# Sheet1.net
KiCad netlist of a schematic drawn in Altium Designer
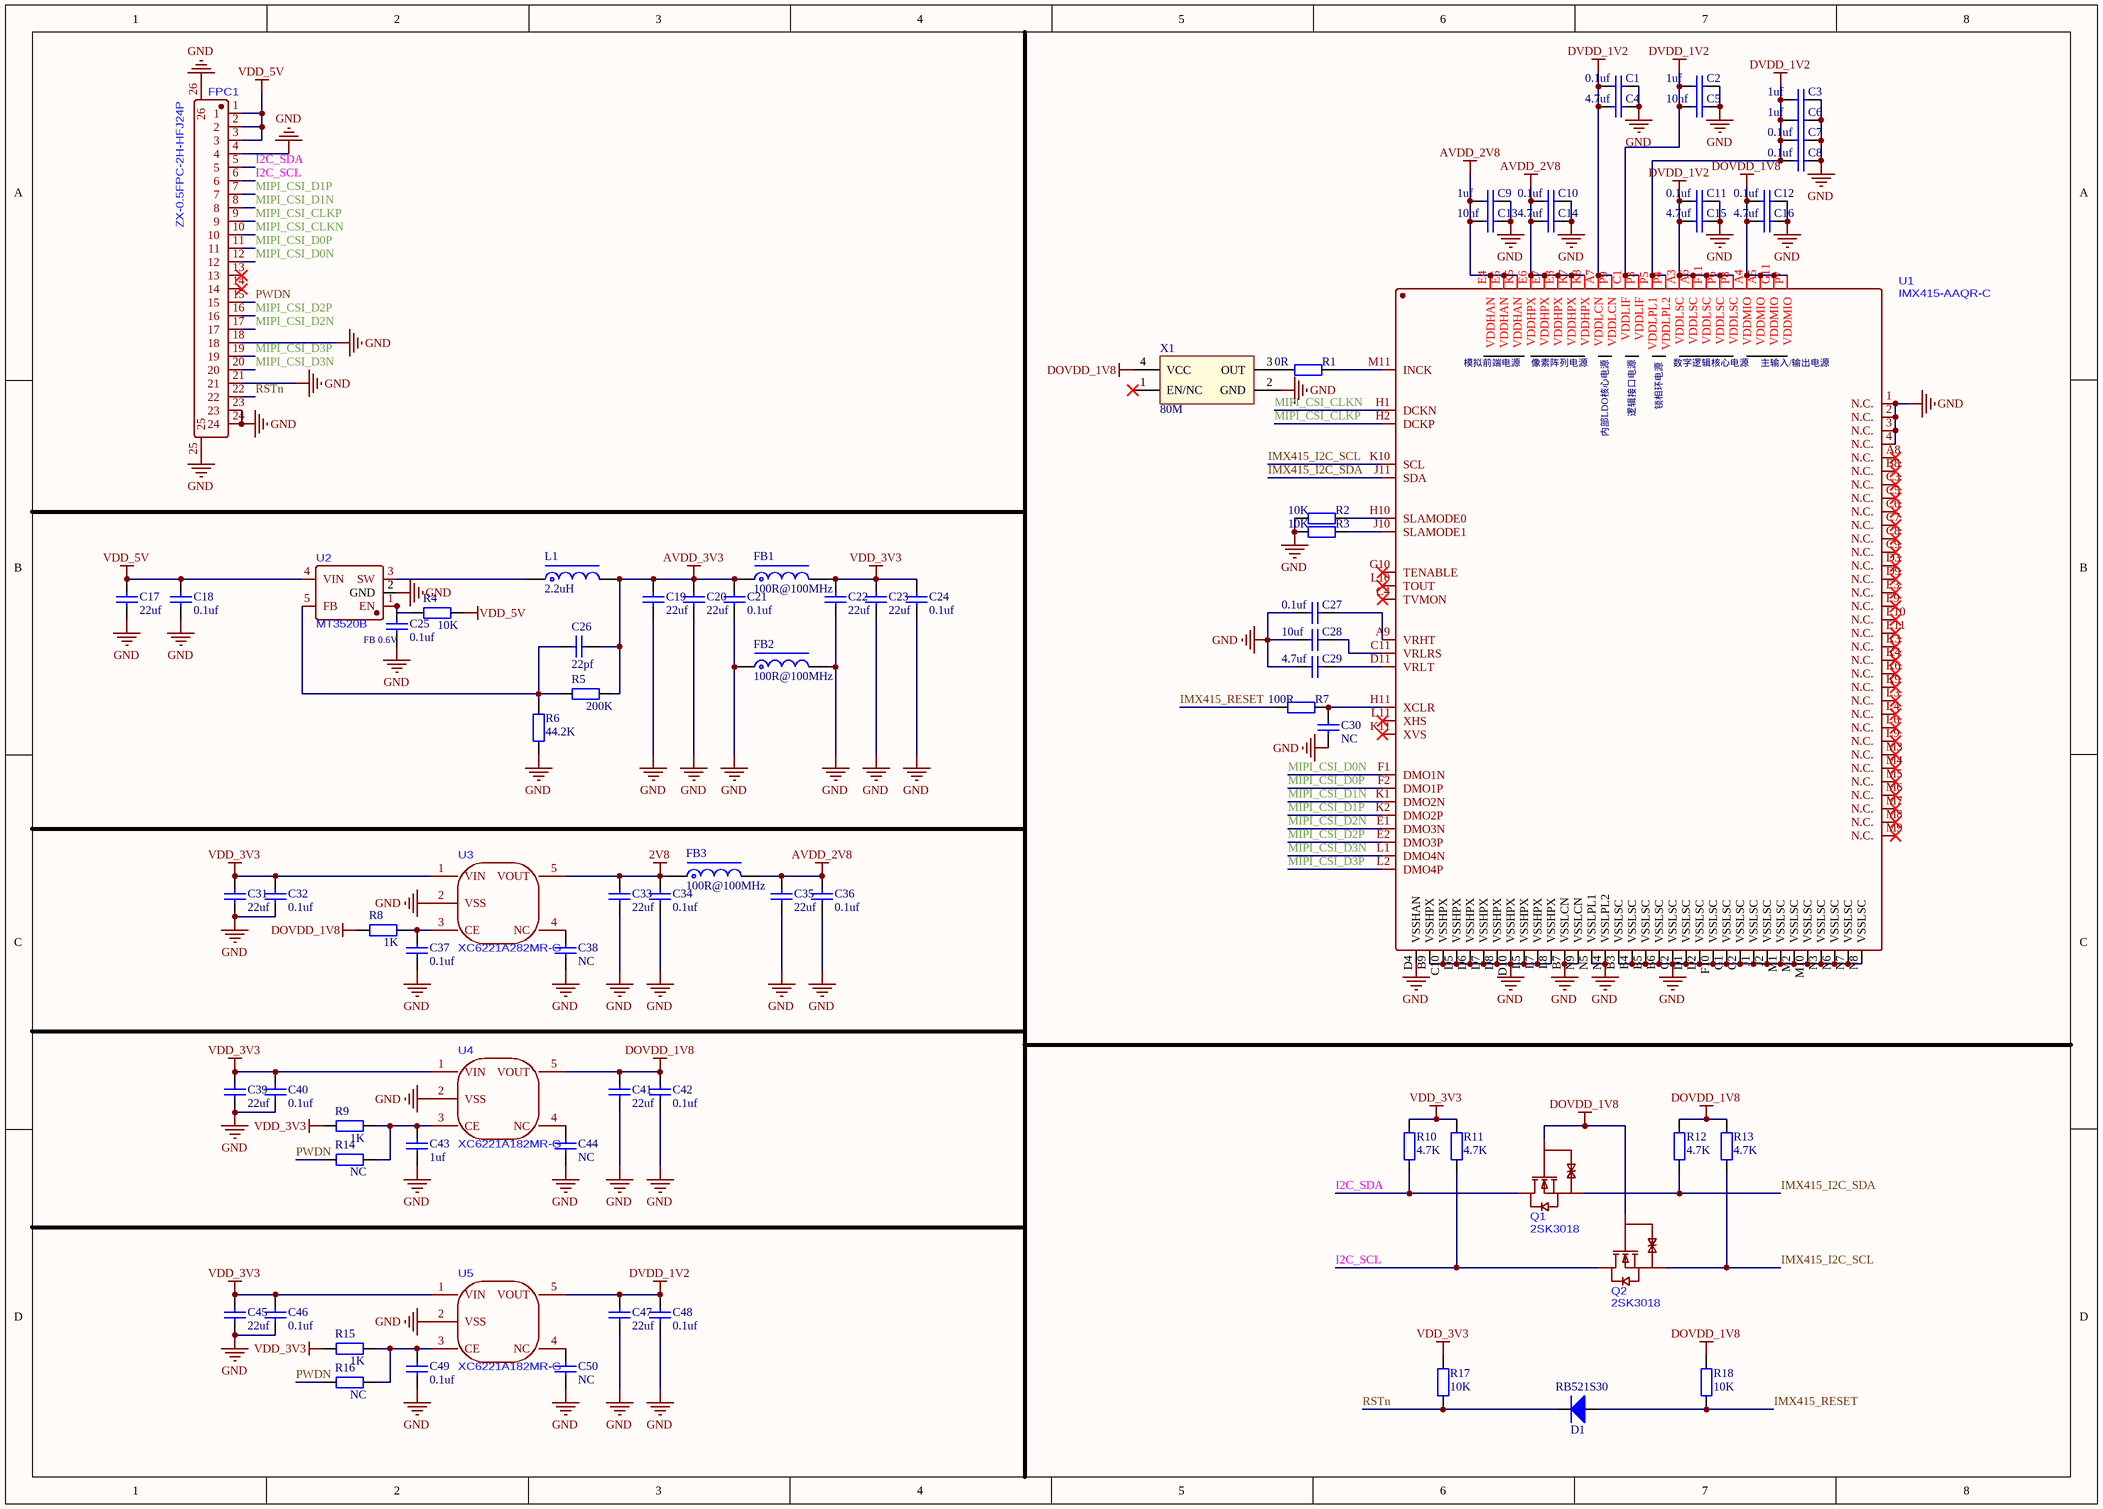
[diagram p0: Sheet1.SchDoc]

(export (version "E")
  (design (tool "Eeschema 10.0.6"))
  (components
    (comp (ref "C1")
      (value "0.1uf")
      (footprint "PCB1:C0402_L")
      (description "贴片电容/MLCC电容")
      (libsource (lib "IMX415") (part "C"))
    )
    (comp (ref "C2")
      (value "1uf")
      (footprint "PCB1:C0402_L")
      (description "贴片电容/MLCC电容")
      (libsource (lib "IMX415") (part "C"))
    )
    (comp (ref "C3")
      (value "1uf")
      (footprint "PCB1:C0402_L")
      (description "贴片电容/MLCC电容")
      (libsource (lib "IMX415") (part "C"))
    )
    (comp (ref "C4")
      (value "4.7uf")
      (footprint "PCB1:C0402_L")
      (description "贴片电容/MLCC电容")
      (libsource (lib "IMX415") (part "C"))
    )
    (comp (ref "C5")
      (value "10nf")
      (footprint "PCB1:C0402_L")
      (description "贴片电容/MLCC电容")
      (libsource (lib "IMX415") (part "C"))
    )
    (comp (ref "C6")
      (value "1uf")
      (footprint "PCB1:C0402_L")
      (description "贴片电容/MLCC电容")
      (libsource (lib "IMX415") (part "C"))
    )
    (comp (ref "C7")
      (value "0.1uf")
      (footprint "PCB1:C0402_L")
      (description "贴片电容/MLCC电容")
      (libsource (lib "IMX415") (part "C"))
    )
    (comp (ref "C8")
      (value "0.1uf")
      (footprint "PCB1:C0402_L")
      (description "贴片电容/MLCC电容")
      (libsource (lib "IMX415") (part "C"))
    )
    (comp (ref "C9")
      (value "1uf")
      (footprint "PCB1:C0402_L")
      (description "贴片电容/MLCC电容")
      (libsource (lib "IMX415") (part "C"))
    )
    (comp (ref "C10")
      (value "0.1uf")
      (footprint "PCB1:C0402_L")
      (description "贴片电容/MLCC电容")
      (libsource (lib "IMX415") (part "C"))
    )
    (comp (ref "C11")
      (value "0.1uf")
      (footprint "PCB1:C0402_L")
      (description "贴片电容/MLCC电容")
      (libsource (lib "IMX415") (part "C"))
    )
    (comp (ref "C12")
      (value "0.1uf")
      (footprint "PCB1:C0402_L")
      (description "贴片电容/MLCC电容")
      (libsource (lib "IMX415") (part "C"))
    )
    (comp (ref "C13")
      (value "10nf")
      (footprint "PCB1:C0402_L")
      (description "贴片电容/MLCC电容")
      (libsource (lib "IMX415") (part "C"))
    )
    (comp (ref "C14")
      (value "4.7uf")
      (footprint "PCB1:C0402_L")
      (description "贴片电容/MLCC电容")
      (libsource (lib "IMX415") (part "C"))
    )
    (comp (ref "C15")
      (value "4.7uf")
      (footprint "PCB1:C0402_L")
      (description "贴片电容/MLCC电容")
      (libsource (lib "IMX415") (part "C"))
    )
    (comp (ref "C16")
      (value "4.7uf")
      (footprint "PCB1:C0402_L")
      (description "贴片电容/MLCC电容")
      (libsource (lib "IMX415") (part "C"))
    )
    (comp (ref "C17")
      (value "22uf")
      (footprint "PCB1:C0603_L")
      (description "贴片电容/MLCC电容")
      (libsource (lib "IMX415") (part "C"))
    )
    (comp (ref "C18")
      (value "0.1uf")
      (footprint "PCB1:C0402_L")
      (description "贴片电容/MLCC电容")
      (libsource (lib "IMX415") (part "C"))
    )
    (comp (ref "C19")
      (value "22uf")
      (footprint "PCB1:C0603_L")
      (description "贴片电容/MLCC电容")
      (libsource (lib "IMX415") (part "C"))
    )
    (comp (ref "C20")
      (value "22uf")
      (footprint "PCB1:C0603_L")
      (description "贴片电容/MLCC电容")
      (libsource (lib "IMX415") (part "C"))
    )
    (comp (ref "C21")
      (value "0.1uf")
      (footprint "PCB1:C0402_L")
      (description "贴片电容/MLCC电容")
      (libsource (lib "IMX415") (part "C"))
    )
    (comp (ref "C22")
      (value "22uf")
      (footprint "PCB1:C0603_L")
      (description "贴片电容/MLCC电容")
      (libsource (lib "IMX415") (part "C"))
    )
    (comp (ref "C23")
      (value "22uf")
      (footprint "PCB1:C0603_L")
      (description "贴片电容/MLCC电容")
      (libsource (lib "IMX415") (part "C"))
    )
    (comp (ref "C24")
      (value "0.1uf")
      (footprint "PCB1:C0402_L")
      (description "贴片电容/MLCC电容")
      (libsource (lib "IMX415") (part "C"))
    )
    (comp (ref "C25")
      (value "0.1uf")
      (footprint "PCB1:C0402_L")
      (description "贴片电容/MLCC电容")
      (libsource (lib "IMX415") (part "C"))
    )
    (comp (ref "C26")
      (value "22pf")
      (footprint "PCB1:C0402_L")
      (description "贴片电容/MLCC电容")
      (libsource (lib "IMX415") (part "C"))
    )
    (comp (ref "C27")
      (value "0.1uf")
      (footprint "PCB1:C0402_L")
      (description "贴片电容/MLCC电容")
      (libsource (lib "IMX415") (part "C"))
    )
    (comp (ref "C28")
      (value "10uf")
      (footprint "PCB1:C0402_L")
      (description "贴片电容/MLCC电容")
      (libsource (lib "IMX415") (part "C"))
    )
    (comp (ref "C29")
      (value "4.7uf")
      (footprint "PCB1:C0402_L")
      (description "贴片电容/MLCC电容")
      (libsource (lib "IMX415") (part "C"))
    )
    (comp (ref "C30")
      (value "NC")
      (footprint "PCB1:C0402_L")
      (description "贴片电容/MLCC电容")
      (libsource (lib "IMX415") (part "C"))
    )
    (comp (ref "C31")
      (value "22uf")
      (footprint "PCB1:C0603_L")
      (description "贴片电容/MLCC电容")
      (libsource (lib "IMX415") (part "C"))
    )
    (comp (ref "C32")
      (value "0.1uf")
      (footprint "PCB1:C0402_L")
      (description "贴片电容/MLCC电容")
      (libsource (lib "IMX415") (part "C"))
    )
    (comp (ref "C33")
      (value "22uf")
      (footprint "PCB1:C0603_L")
      (description "贴片电容/MLCC电容")
      (libsource (lib "IMX415") (part "C"))
    )
    (comp (ref "C34")
      (value "0.1uf")
      (footprint "PCB1:C0402_L")
      (description "贴片电容/MLCC电容")
      (libsource (lib "IMX415") (part "C"))
    )
    (comp (ref "C35")
      (value "22uf")
      (footprint "PCB1:C0603_L")
      (description "贴片电容/MLCC电容")
      (libsource (lib "IMX415") (part "C"))
    )
    (comp (ref "C36")
      (value "0.1uf")
      (footprint "PCB1:C0402_L")
      (description "贴片电容/MLCC电容")
      (libsource (lib "IMX415") (part "C"))
    )
    (comp (ref "C37")
      (value "0.1uf")
      (footprint "PCB1:C0402_L")
      (description "贴片电容/MLCC电容")
      (libsource (lib "IMX415") (part "C"))
    )
    (comp (ref "C38")
      (value "NC")
      (footprint "PCB1:C0402_L")
      (description "贴片电容/MLCC电容")
      (libsource (lib "IMX415") (part "C"))
    )
    (comp (ref "C39")
      (value "22uf")
      (footprint "PCB1:C0603_L")
      (description "贴片电容/MLCC电容")
      (libsource (lib "IMX415") (part "C"))
    )
    (comp (ref "C40")
      (value "0.1uf")
      (footprint "PCB1:C0402_L")
      (description "贴片电容/MLCC电容")
      (libsource (lib "IMX415") (part "C"))
    )
    (comp (ref "C41")
      (value "22uf")
      (footprint "PCB1:C0603_L")
      (description "贴片电容/MLCC电容")
      (libsource (lib "IMX415") (part "C"))
    )
    (comp (ref "C42")
      (value "0.1uf")
      (footprint "PCB1:C0402_L")
      (description "贴片电容/MLCC电容")
      (libsource (lib "IMX415") (part "C"))
    )
    (comp (ref "C43")
      (value "1uf")
      (footprint "PCB1:C0402_L")
      (description "贴片电容/MLCC电容")
      (libsource (lib "IMX415") (part "C"))
    )
    (comp (ref "C44")
      (value "NC")
      (footprint "PCB1:C0402_L")
      (description "贴片电容/MLCC电容")
      (libsource (lib "IMX415") (part "C"))
    )
    (comp (ref "C45")
      (value "22uf")
      (footprint "PCB1:C0603_L")
      (description "贴片电容/MLCC电容")
      (libsource (lib "IMX415") (part "C"))
    )
    (comp (ref "C46")
      (value "0.1uf")
      (footprint "PCB1:C0402_L")
      (description "贴片电容/MLCC电容")
      (libsource (lib "IMX415") (part "C"))
    )
    (comp (ref "C47")
      (value "22uf")
      (footprint "PCB1:C0603_L")
      (description "贴片电容/MLCC电容")
      (libsource (lib "IMX415") (part "C"))
    )
    (comp (ref "C48")
      (value "0.1uf")
      (footprint "PCB1:C0402_L")
      (description "贴片电容/MLCC电容")
      (libsource (lib "IMX415") (part "C"))
    )
    (comp (ref "C49")
      (value "0.1uf")
      (footprint "PCB1:C0402_L")
      (description "贴片电容/MLCC电容")
      (libsource (lib "IMX415") (part "C"))
    )
    (comp (ref "C50")
      (value "NC")
      (footprint "PCB1:C0402_L")
      (description "贴片电容/MLCC电容")
      (libsource (lib "IMX415") (part "C"))
    )
    (comp (ref "D1") (value "RB521S30") (footprint "PCB1:SOD-323") (libsource (lib "IMX415") (part "TVS")))
    (comp (ref "FB1")
      (value "100R@100MHz")
      (footprint "PCB1:FB0603")
      (description "贴片磁珠")
      (libsource (lib "IMX415") (part "FB"))
    )
    (comp (ref "FB2")
      (value "100R@100MHz")
      (footprint "PCB1:FB0603")
      (description "贴片磁珠")
      (libsource (lib "IMX415") (part "FB"))
    )
    (comp (ref "FB3")
      (value "100R@100MHz")
      (footprint "PCB1:FB0603")
      (description "贴片磁珠")
      (libsource (lib "IMX415") (part "FB"))
    )
    (comp (ref "FPC1")
      (value "ZX-0.5FPC-2H-HFJ24P")
      (footprint "PCB1:FPC-SMD_24P-P0.50_ZX-0.5FPC-2H-HFJ24P")
      (libsource (lib "IMX415") (part "ZX-0.5FPC-2H-HFJ24P"))
    )
    (comp (ref "L1")
      (value "2.2uH")
      (footprint "PCB1:NR2520")
      (description "太诱-NR磁胶电感")
      (libsource (lib "IMX415") (part "L-NR"))
    )
    (comp (ref "Q1")
      (value "2SK3018")
      (footprint "PCB1:SOT-23-3_L2.9-W1.3-P1.90-LS2.4-BR")
      (libsource (lib "IMX415") (part "2SK3018"))
    )
    (comp (ref "Q2")
      (value "2SK3018")
      (footprint "PCB1:SOT-23-3_L2.9-W1.3-P1.90-LS2.4-BR")
      (libsource (lib "IMX415") (part "2SK3018"))
    )
    (comp (ref "R1")
      (value "0R")
      (footprint "PCB1:R0402_L")
      (description "贴片电阻")
      (libsource (lib "IMX415") (part "R"))
    )
    (comp (ref "R2")
      (value "10K")
      (footprint "PCB1:R0402_L")
      (description "贴片电阻")
      (libsource (lib "IMX415") (part "R"))
    )
    (comp (ref "R3")
      (value "10K")
      (footprint "PCB1:R0402_L")
      (description "贴片电阻")
      (libsource (lib "IMX415") (part "R"))
    )
    (comp (ref "R4")
      (value "10K")
      (footprint "PCB1:R0402_L")
      (description "贴片电阻")
      (libsource (lib "IMX415") (part "R"))
    )
    (comp (ref "R5")
      (value "200K")
      (footprint "PCB1:R0402_L")
      (description "贴片电阻")
      (libsource (lib "IMX415") (part "R"))
    )
    (comp (ref "R6")
      (value "44.2K")
      (footprint "PCB1:R0402_L")
      (description "贴片电阻")
      (libsource (lib "IMX415") (part "R"))
    )
    (comp (ref "R7")
      (value "100R")
      (footprint "PCB1:R0402_L")
      (description "贴片电阻")
      (libsource (lib "IMX415") (part "R"))
    )
    (comp (ref "R8")
      (value "1K")
      (footprint "PCB1:R0402_L")
      (description "贴片电阻")
      (libsource (lib "IMX415") (part "R"))
    )
    (comp (ref "R9")
      (value "1K")
      (footprint "PCB1:R0402_L")
      (description "贴片电阻")
      (libsource (lib "IMX415") (part "R"))
    )
    (comp (ref "R10")
      (value "4.7K")
      (footprint "PCB1:R0402_L")
      (description "贴片电阻")
      (libsource (lib "IMX415") (part "R"))
    )
    (comp (ref "R11")
      (value "4.7K")
      (footprint "PCB1:R0402_L")
      (description "贴片电阻")
      (libsource (lib "IMX415") (part "R"))
    )
    (comp (ref "R12")
      (value "4.7K")
      (footprint "PCB1:R0402_L")
      (description "贴片电阻")
      (libsource (lib "IMX415") (part "R"))
    )
    (comp (ref "R13")
      (value "4.7K")
      (footprint "PCB1:R0402_L")
      (description "贴片电阻")
      (libsource (lib "IMX415") (part "R"))
    )
    (comp (ref "R14")
      (value "NC")
      (footprint "PCB1:R0402_L")
      (description "贴片电阻")
      (libsource (lib "IMX415") (part "R"))
    )
    (comp (ref "R15")
      (value "1K")
      (footprint "PCB1:R0402_L")
      (description "贴片电阻")
      (libsource (lib "IMX415") (part "R"))
    )
    (comp (ref "R16")
      (value "NC")
      (footprint "PCB1:R0402_L")
      (description "贴片电阻")
      (libsource (lib "IMX415") (part "R"))
    )
    (comp (ref "R17")
      (value "10K")
      (footprint "PCB1:R0402_L")
      (description "贴片电阻")
      (libsource (lib "IMX415") (part "R"))
    )
    (comp (ref "R18")
      (value "10K")
      (footprint "PCB1:R0402_L")
      (description "贴片电阻")
      (libsource (lib "IMX415") (part "R"))
    )
    (comp (ref "U1")
      (value "IMX415-AAQR-C")
      (footprint "PCB1:BGA-110_L12.0-W9.3-BL_IMX415-AAQR-C")
      (libsource (lib "IMX415") (part "IMX415-AAQR-C"))
    )
    (comp (ref "U2")
      (value "MT3520B")
      (footprint "PCB1:SOT-23-5_L3.0-W1.7-P0.95-LS2.8-BR")
      (libsource (lib "IMX415") (part "MT3520B"))
    )
    (comp (ref "U3")
      (value "XC6221A282MR-G")
      (footprint "PCB1:SOT-23-5_L3.0-W1.7-P0.95-LS2.8-BR")
      (libsource (lib "IMX415") (part "XC6221A282MR-G"))
    )
    (comp (ref "U4")
      (value "XC6221A182MR-G")
      (footprint "PCB1:SOT-23-5_L3.0-W1.7-P0.95-LS2.8-BR")
      (libsource (lib "IMX415") (part "XC6221A282MR-G"))
    )
    (comp (ref "U5")
      (value "XC6221A182MR-G")
      (footprint "PCB1:SOT-23-5_L3.0-W1.7-P0.95-LS2.8-BR")
      (libsource (lib "IMX415") (part "XC6221A282MR-G"))
    )
    (comp (ref "X1")
      (value "80M")
      (footprint "PCB1:OSC-3225-4P")
      (description "4脚有源晶振(振荡器)")
      (libsource (lib "IMX415") (part "XTAL-ACT-4P"))
    )
  )
  (nets
    (net (code "1") (name "/I2C_SCL") (class "Default")
      (node (ref "FPC1") (pin "6") (pinfunction "6_6") (pintype "passive"))
      (node (ref "Q2") (pin "3") (pinfunction "D_3") (pintype "passive"))
      (node (ref "R11") (pin "1") (pinfunction "1_1") (pintype "passive"))
    )
    (net (code "2") (name "/I2C_SDA") (class "Default")
      (node (ref "FPC1") (pin "5") (pinfunction "5_5") (pintype "passive"))
      (node (ref "Q1") (pin "3") (pinfunction "D_3") (pintype "passive"))
      (node (ref "R10") (pin "1") (pinfunction "1_1") (pintype "passive"))
    )
    (net (code "3") (name "/IMX415_I2C_SCL") (class "Default")
      (node (ref "Q2") (pin "2") (pinfunction "S_2") (pintype "passive"))
      (node (ref "R13") (pin "1") (pinfunction "1_1") (pintype "passive"))
      (node (ref "U1") (pin "K10") (pinfunction "SCL_K10") (pintype "passive"))
    )
    (net (code "4") (name "/IMX415_I2C_SDA") (class "Default")
      (node (ref "Q1") (pin "2") (pinfunction "S_2") (pintype "passive"))
      (node (ref "R12") (pin "1") (pinfunction "1_1") (pintype "passive"))
      (node (ref "U1") (pin "J11") (pinfunction "SDA_J11") (pintype "passive"))
    )
    (net (code "5") (name "/IMX415_RESET") (class "Default")
      (node (ref "D1") (pin "1") (pinfunction "A_1") (pintype "passive"))
      (node (ref "R18") (pin "1") (pinfunction "1_1") (pintype "passive"))
      (node (ref "R7") (pin "1") (pinfunction "1_1") (pintype "passive"))
    )
    (net (code "6") (name "/MIPI_CSI_CLKN") (class "Default")
      (node (ref "FPC1") (pin "10") (pinfunction "10_10") (pintype "passive"))
      (node (ref "U1") (pin "H1") (pinfunction "DCKN_H1") (pintype "passive"))
    )
    (net (code "7") (name "/MIPI_CSI_CLKP") (class "Default")
      (node (ref "FPC1") (pin "9") (pinfunction "9_9") (pintype "passive"))
      (node (ref "U1") (pin "H2") (pinfunction "DCKP_H2") (pintype "passive"))
    )
    (net (code "8") (name "/MIPI_CSI_D0N") (class "Default")
      (node (ref "FPC1") (pin "12") (pinfunction "12_12") (pintype "passive"))
      (node (ref "U1") (pin "F1") (pinfunction "DMO1N_F1") (pintype "passive"))
    )
    (net (code "9") (name "/MIPI_CSI_D0P") (class "Default")
      (node (ref "FPC1") (pin "11") (pinfunction "11_11") (pintype "passive"))
      (node (ref "U1") (pin "F2") (pinfunction "DMO1P_F2") (pintype "passive"))
    )
    (net (code "10") (name "/MIPI_CSI_D1N") (class "Default")
      (node (ref "FPC1") (pin "8") (pinfunction "8_8") (pintype "passive"))
      (node (ref "U1") (pin "K1") (pinfunction "DMO2N_K1") (pintype "passive"))
    )
    (net (code "11") (name "/MIPI_CSI_D1P") (class "Default")
      (node (ref "FPC1") (pin "7") (pinfunction "7_7") (pintype "passive"))
      (node (ref "U1") (pin "K2") (pinfunction "DMO2P_K2") (pintype "passive"))
    )
    (net (code "12") (name "/MIPI_CSI_D2N") (class "Default")
      (node (ref "FPC1") (pin "17") (pinfunction "17_17") (pintype "passive"))
      (node (ref "U1") (pin "E1") (pinfunction "DMO3N_E1") (pintype "passive"))
    )
    (net (code "13") (name "/MIPI_CSI_D2P") (class "Default")
      (node (ref "FPC1") (pin "16") (pinfunction "16_16") (pintype "passive"))
      (node (ref "U1") (pin "E2") (pinfunction "DMO3P_E2") (pintype "passive"))
    )
    (net (code "14") (name "/MIPI_CSI_D3N") (class "Default")
      (node (ref "FPC1") (pin "20") (pinfunction "20_20") (pintype "passive"))
      (node (ref "U1") (pin "L1") (pinfunction "DMO4N_L1") (pintype "passive"))
    )
    (net (code "15") (name "/MIPI_CSI_D3P") (class "Default")
      (node (ref "FPC1") (pin "19") (pinfunction "19_19") (pintype "passive"))
      (node (ref "U1") (pin "L2") (pinfunction "DMO4P_L2") (pintype "passive"))
    )
    (net (code "16") (name "/PWDN") (class "Default")
      (node (ref "FPC1") (pin "15") (pinfunction "15_15") (pintype "passive"))
      (node (ref "R14") (pin "1") (pinfunction "1_1") (pintype "passive"))
      (node (ref "R16") (pin "1") (pinfunction "1_1") (pintype "passive"))
    )
    (net (code "17") (name "/RSTn") (class "Default")
      (node (ref "D1") (pin "2") (pinfunction "K_2") (pintype "passive"))
      (node (ref "FPC1") (pin "22") (pinfunction "22_22") (pintype "passive"))
      (node (ref "R17") (pin "1") (pinfunction "1_1") (pintype "passive"))
    )
    (net (code "18") (name "2V8") (class "Default")
      (node (ref "C33") (pin "2") (pinfunction "2_2") (pintype "passive"))
      (node (ref "C34") (pin "2") (pinfunction "2_2") (pintype "passive"))
      (node (ref "FB3") (pin "1") (pinfunction "1_1") (pintype "passive"))
      (node (ref "U3") (pin "5") (pinfunction "VOUT_5") (pintype "passive"))
    )
    (net (code "19") (name "AVDD_2V8") (class "Default")
      (node (ref "C10") (pin "2") (pinfunction "2_2") (pintype "passive"))
      (node (ref "C13") (pin "2") (pinfunction "2_2") (pintype "passive"))
      (node (ref "C14") (pin "2") (pinfunction "2_2") (pintype "passive"))
      (node (ref "C35") (pin "2") (pinfunction "2_2") (pintype "passive"))
      (node (ref "C36") (pin "2") (pinfunction "2_2") (pintype "passive"))
      (node (ref "C9") (pin "2") (pinfunction "2_2") (pintype "passive"))
      (node (ref "FB3") (pin "2") (pinfunction "2_2") (pintype "passive"))
      (node (ref "U1") (pin "E4") (pinfunction "VDDHAN_E4") (pintype "passive"))
      (node (ref "U1") (pin "E5") (pinfunction "VDDHAN_E5") (pintype "passive"))
      (node (ref "U1") (pin "E6") (pinfunction "VDDHPX_E6") (pintype "passive"))
      (node (ref "U1") (pin "E7") (pinfunction "VDDHPX_E7") (pintype "passive"))
      (node (ref "U1") (pin "E8") (pinfunction "VDDHPX_E8") (pintype "passive"))
      (node (ref "U1") (pin "K5") (pinfunction "VDDHAN_K5") (pintype "passive"))
      (node (ref "U1") (pin "K7") (pinfunction "VDDHPX_K7") (pintype "passive"))
      (node (ref "U1") (pin "K8") (pinfunction "VDDHPX_K8") (pintype "passive"))
    )
    (net (code "20") (name "AVDD_3V3") (class "Default")
      (node (ref "C19") (pin "2") (pinfunction "2_2") (pintype "passive"))
      (node (ref "C20") (pin "2") (pinfunction "2_2") (pintype "passive"))
      (node (ref "C21") (pin "2") (pinfunction "2_2") (pintype "passive"))
      (node (ref "C26") (pin "1") (pinfunction "1_1") (pintype "passive"))
      (node (ref "FB1") (pin "1") (pinfunction "1_1") (pintype "passive"))
      (node (ref "L1") (pin "2") (pinfunction "2_2") (pintype "passive"))
      (node (ref "R5") (pin "2") (pinfunction "2_2") (pintype "passive"))
    )
    (net (code "21") (name "DOVDD_1V8") (class "Default")
      (node (ref "C12") (pin "2") (pinfunction "2_2") (pintype "passive"))
      (node (ref "C16") (pin "2") (pinfunction "2_2") (pintype "passive"))
      (node (ref "C41") (pin "2") (pinfunction "2_2") (pintype "passive"))
      (node (ref "C42") (pin "2") (pinfunction "2_2") (pintype "passive"))
      (node (ref "Q1") (pin "1") (pinfunction "G_1") (pintype "passive"))
      (node (ref "Q2") (pin "1") (pinfunction "G_1") (pintype "passive"))
      (node (ref "R12") (pin "2") (pinfunction "2_2") (pintype "passive"))
      (node (ref "R13") (pin "2") (pinfunction "2_2") (pintype "passive"))
      (node (ref "R18") (pin "2") (pinfunction "2_2") (pintype "passive"))
      (node (ref "R8") (pin "1") (pinfunction "1_1") (pintype "passive"))
      (node (ref "U1") (pin "A4") (pinfunction "VDDMIO_A4") (pintype "passive"))
      (node (ref "U1") (pin "A5") (pinfunction "VDDMIO_A5") (pintype "passive"))
      (node (ref "U1") (pin "G11") (pinfunction "VDDMIO_G11") (pintype "passive"))
      (node (ref "U1") (pin "P7") (pinfunction "VDDMIO_P7") (pintype "passive"))
      (node (ref "U4") (pin "5") (pinfunction "VOUT_5") (pintype "passive"))
      (node (ref "X1") (pin "4") (pinfunction "VCC_4") (pintype "passive"))
    )
    (net (code "22") (name "DVDD_1V2") (class "Default")
      (node (ref "C1") (pin "2") (pinfunction "2_2") (pintype "passive"))
      (node (ref "C11") (pin "2") (pinfunction "2_2") (pintype "passive"))
      (node (ref "C15") (pin "2") (pinfunction "2_2") (pintype "passive"))
      (node (ref "C2") (pin "2") (pinfunction "2_2") (pintype "passive"))
      (node (ref "C3") (pin "2") (pinfunction "2_2") (pintype "passive"))
      (node (ref "C4") (pin "2") (pinfunction "2_2") (pintype "passive"))
      (node (ref "C47") (pin "2") (pinfunction "2_2") (pintype "passive"))
      (node (ref "C48") (pin "2") (pinfunction "2_2") (pintype "passive"))
      (node (ref "C5") (pin "2") (pinfunction "2_2") (pintype "passive"))
      (node (ref "C6") (pin "2") (pinfunction "2_2") (pintype "passive"))
      (node (ref "C7") (pin "2") (pinfunction "2_2") (pintype "passive"))
      (node (ref "C8") (pin "2") (pinfunction "2_2") (pintype "passive"))
      (node (ref "U1") (pin "A3") (pinfunction "VDDLSC_A3") (pintype "passive"))
      (node (ref "U1") (pin "A6") (pinfunction "VDDLSC_A6") (pintype "passive"))
      (node (ref "U1") (pin "A7") (pinfunction "VDDLCN_A7") (pintype "passive"))
      (node (ref "U1") (pin "C1") (pinfunction "VDDLIF_C1") (pintype "passive"))
      (node (ref "U1") (pin "F11") (pinfunction "VDDLSC_F11") (pintype "passive"))
      (node (ref "U1") (pin "P3") (pinfunction "VDDLIF_P3") (pintype "passive"))
      (node (ref "U1") (pin "P4") (pinfunction "VDDLPL2_P4") (pintype "passive"))
      (node (ref "U1") (pin "P5") (pinfunction "VDDLPL1_P5") (pintype "passive"))
      (node (ref "U1") (pin "P6") (pinfunction "VDDLSC_P6") (pintype "passive"))
      (node (ref "U1") (pin "P8") (pinfunction "VDDLSC_P8") (pintype "passive"))
      (node (ref "U1") (pin "P9") (pinfunction "VDDLCN_P9") (pintype "passive"))
      (node (ref "U5") (pin "5") (pinfunction "VOUT_5") (pintype "passive"))
    )
    (net (code "23") (name "GND") (class "Default")
      (node (ref "C1") (pin "1") (pinfunction "1_1") (pintype "passive"))
      (node (ref "C10") (pin "1") (pinfunction "1_1") (pintype "passive"))
      (node (ref "C11") (pin "1") (pinfunction "1_1") (pintype "passive"))
      (node (ref "C12") (pin "1") (pinfunction "1_1") (pintype "passive"))
      (node (ref "C13") (pin "1") (pinfunction "1_1") (pintype "passive"))
      (node (ref "C14") (pin "1") (pinfunction "1_1") (pintype "passive"))
      (node (ref "C15") (pin "1") (pinfunction "1_1") (pintype "passive"))
      (node (ref "C16") (pin "1") (pinfunction "1_1") (pintype "passive"))
      (node (ref "C17") (pin "1") (pinfunction "1_1") (pintype "passive"))
      (node (ref "C18") (pin "1") (pinfunction "1_1") (pintype "passive"))
      (node (ref "C19") (pin "1") (pinfunction "1_1") (pintype "passive"))
      (node (ref "C2") (pin "1") (pinfunction "1_1") (pintype "passive"))
      (node (ref "C20") (pin "1") (pinfunction "1_1") (pintype "passive"))
      (node (ref "C21") (pin "1") (pinfunction "1_1") (pintype "passive"))
      (node (ref "C22") (pin "1") (pinfunction "1_1") (pintype "passive"))
      (node (ref "C23") (pin "1") (pinfunction "1_1") (pintype "passive"))
      (node (ref "C24") (pin "1") (pinfunction "1_1") (pintype "passive"))
      (node (ref "C25") (pin "1") (pinfunction "1_1") (pintype "passive"))
      (node (ref "C27") (pin "2") (pinfunction "2_2") (pintype "passive"))
      (node (ref "C28") (pin "2") (pinfunction "2_2") (pintype "passive"))
      (node (ref "C29") (pin "2") (pinfunction "2_2") (pintype "passive"))
      (node (ref "C3") (pin "1") (pinfunction "1_1") (pintype "passive"))
      (node (ref "C30") (pin "1") (pinfunction "1_1") (pintype "passive"))
      (node (ref "C31") (pin "1") (pinfunction "1_1") (pintype "passive"))
      (node (ref "C32") (pin "1") (pinfunction "1_1") (pintype "passive"))
      (node (ref "C33") (pin "1") (pinfunction "1_1") (pintype "passive"))
      (node (ref "C34") (pin "1") (pinfunction "1_1") (pintype "passive"))
      (node (ref "C35") (pin "1") (pinfunction "1_1") (pintype "passive"))
      (node (ref "C36") (pin "1") (pinfunction "1_1") (pintype "passive"))
      (node (ref "C37") (pin "1") (pinfunction "1_1") (pintype "passive"))
      (node (ref "C38") (pin "1") (pinfunction "1_1") (pintype "passive"))
      (node (ref "C39") (pin "1") (pinfunction "1_1") (pintype "passive"))
      (node (ref "C4") (pin "1") (pinfunction "1_1") (pintype "passive"))
      (node (ref "C40") (pin "1") (pinfunction "1_1") (pintype "passive"))
      (node (ref "C41") (pin "1") (pinfunction "1_1") (pintype "passive"))
      (node (ref "C42") (pin "1") (pinfunction "1_1") (pintype "passive"))
      (node (ref "C43") (pin "1") (pinfunction "1_1") (pintype "passive"))
      (node (ref "C44") (pin "1") (pinfunction "1_1") (pintype "passive"))
      (node (ref "C45") (pin "1") (pinfunction "1_1") (pintype "passive"))
      (node (ref "C46") (pin "1") (pinfunction "1_1") (pintype "passive"))
      (node (ref "C47") (pin "1") (pinfunction "1_1") (pintype "passive"))
      (node (ref "C48") (pin "1") (pinfunction "1_1") (pintype "passive"))
      (node (ref "C49") (pin "1") (pinfunction "1_1") (pintype "passive"))
      (node (ref "C5") (pin "1") (pinfunction "1_1") (pintype "passive"))
      (node (ref "C50") (pin "1") (pinfunction "1_1") (pintype "passive"))
      (node (ref "C6") (pin "1") (pinfunction "1_1") (pintype "passive"))
      (node (ref "C7") (pin "1") (pinfunction "1_1") (pintype "passive"))
      (node (ref "C8") (pin "1") (pinfunction "1_1") (pintype "passive"))
      (node (ref "C9") (pin "1") (pinfunction "1_1") (pintype "passive"))
      (node (ref "FB2") (pin "1") (pinfunction "1_1") (pintype "passive"))
      (node (ref "FB2") (pin "2") (pinfunction "2_2") (pintype "passive"))
      (node (ref "FPC1") (pin "18") (pinfunction "18_18") (pintype "passive"))
      (node (ref "FPC1") (pin "21") (pinfunction "21_21") (pintype "passive"))
      (node (ref "FPC1") (pin "23") (pinfunction "23_23") (pintype "passive"))
      (node (ref "FPC1") (pin "24") (pinfunction "24_24") (pintype "passive"))
      (node (ref "FPC1") (pin "25") (pinfunction "25_25") (pintype "passive"))
      (node (ref "FPC1") (pin "26") (pinfunction "26_26") (pintype "passive"))
      (node (ref "FPC1") (pin "4") (pinfunction "4_4") (pintype "passive"))
      (node (ref "R2") (pin "1") (pinfunction "1_1") (pintype "passive"))
      (node (ref "R3") (pin "1") (pinfunction "1_1") (pintype "passive"))
      (node (ref "R6") (pin "1") (pinfunction "1_1") (pintype "passive"))
      (node (ref "U1") (pin "1") (pinfunction "N.C._1") (pintype "passive"))
      (node (ref "U1") (pin "2") (pinfunction "N.C._2") (pintype "passive"))
      (node (ref "U1") (pin "3") (pinfunction "N.C._3") (pintype "passive"))
      (node (ref "U1") (pin "4") (pinfunction "N.C._4") (pintype "passive"))
      (node (ref "U1") (pin "B3") (pinfunction "VSSLSC_B3") (pintype "passive"))
      (node (ref "U1") (pin "B4") (pinfunction "VSSLSC_B4") (pintype "passive"))
      (node (ref "U1") (pin "B5") (pinfunction "VSSLSC_B5") (pintype "passive"))
      (node (ref "U1") (pin "B6") (pinfunction "VSSLSC_B6") (pintype "passive"))
      (node (ref "U1") (pin "B7") (pinfunction "VSSLCN_B7") (pintype "passive"))
      (node (ref "U1") (pin "B9") (pinfunction "VSSHPX_B9") (pintype "passive"))
      (node (ref "U1") (pin "C10") (pinfunction "VSSHPX_C10") (pintype "passive"))
      (node (ref "U1") (pin "C2") (pinfunction "VSSLSC_C2") (pintype "passive"))
      (node (ref "U1") (pin "D1") (pinfunction "VSSLSC_D1") (pintype "passive"))
      (node (ref "U1") (pin "D10") (pinfunction "VSSHPX_D10") (pintype "passive"))
      (node (ref "U1") (pin "D2") (pinfunction "VSSLSC_D2") (pintype "passive"))
      (node (ref "U1") (pin "D4") (pinfunction "VSSHAN_D4") (pintype "passive"))
      (node (ref "U1") (pin "D5") (pinfunction "VSSHPX_D5") (pintype "passive"))
      (node (ref "U1") (pin "D6") (pinfunction "VSSHPX_D6") (pintype "passive"))
      (node (ref "U1") (pin "D7") (pinfunction "VSSHPX_D7") (pintype "passive"))
      (node (ref "U1") (pin "D8") (pinfunction "VSSHPX_D8") (pintype "passive"))
      (node (ref "U1") (pin "F10") (pinfunction "VSSLSC_F10") (pintype "passive"))
      (node (ref "U1") (pin "G1") (pinfunction "VSSLSC_G1") (pintype "passive"))
      (node (ref "U1") (pin "G2") (pinfunction "VSSLSC_G2") (pintype "passive"))
      (node (ref "U1") (pin "J1") (pinfunction "VSSLSC_J1") (pintype "passive"))
      (node (ref "U1") (pin "J2") (pinfunction "VSSLSC_J2") (pintype "passive"))
      (node (ref "U1") (pin "L5") (pinfunction "VSSHPX_L5") (pintype "passive"))
      (node (ref "U1") (pin "L7") (pinfunction "VSSHPX_L7") (pintype "passive"))
      (node (ref "U1") (pin "L8") (pinfunction "VSSHPX_L8") (pintype "passive"))
      (node (ref "U1") (pin "M1") (pinfunction "VSSLSC_M1") (pintype "passive"))
      (node (ref "U1") (pin "M10") (pinfunction "VSSLSC_M10") (pintype "passive"))
      (node (ref "U1") (pin "M2") (pinfunction "VSSLSC_M2") (pintype "passive"))
      (node (ref "U1") (pin "N3") (pinfunction "VSSLSC_N3") (pintype "passive"))
      (node (ref "U1") (pin "N4") (pinfunction "VSSLPL2_N4") (pintype "passive"))
      (node (ref "U1") (pin "N5") (pinfunction "VSSLPL1_N5") (pintype "passive"))
      (node (ref "U1") (pin "N6") (pinfunction "VSSLSC_N6") (pintype "passive"))
      (node (ref "U1") (pin "N7") (pinfunction "VSSLSC_N7") (pintype "passive"))
      (node (ref "U1") (pin "N8") (pinfunction "VSSLSC_N8") (pintype "passive"))
      (node (ref "U1") (pin "N9") (pinfunction "VSSLCN_N9") (pintype "passive"))
      (node (ref "U2") (pin "2") (pinfunction "GND_2") (pintype "passive"))
      (node (ref "U3") (pin "2") (pinfunction "VSS_2") (pintype "passive"))
      (node (ref "U4") (pin "2") (pinfunction "VSS_2") (pintype "passive"))
      (node (ref "U5") (pin "2") (pinfunction "VSS_2") (pintype "passive"))
      (node (ref "X1") (pin "2") (pinfunction "GND_2") (pintype "passive"))
    )
    (net (code "24") (name "Net-(U1-INCK)") (class "Default")
      (node (ref "R1") (pin "2") (pinfunction "2_2") (pintype "passive"))
      (node (ref "U1") (pin "M11") (pinfunction "INCK_M11") (pintype "passive"))
    )
    (net (code "25") (name "Net-(U1-SLAMODE0)") (class "Default")
      (node (ref "R2") (pin "2") (pinfunction "2_2") (pintype "passive"))
      (node (ref "U1") (pin "H10") (pinfunction "SLAMODE0_H10") (pintype "passive"))
    )
    (net (code "26") (name "Net-(U1-SLAMODE1)") (class "Default")
      (node (ref "R3") (pin "2") (pinfunction "2_2") (pintype "passive"))
      (node (ref "U1") (pin "J10") (pinfunction "SLAMODE1_J10") (pintype "passive"))
    )
    (net (code "27") (name "Net-(U1-VRHT)") (class "Default")
      (node (ref "C27") (pin "1") (pinfunction "1_1") (pintype "passive"))
      (node (ref "U1") (pin "A9") (pinfunction "VRHT_A9") (pintype "passive"))
    )
    (net (code "28") (name "Net-(U1-VRLRS)") (class "Default")
      (node (ref "C28") (pin "1") (pinfunction "1_1") (pintype "passive"))
      (node (ref "U1") (pin "C11") (pinfunction "VRLRS_C11") (pintype "passive"))
    )
    (net (code "29") (name "Net-(U1-VRLT)") (class "Default")
      (node (ref "C29") (pin "1") (pinfunction "1_1") (pintype "passive"))
      (node (ref "U1") (pin "D11") (pinfunction "VRLT_D11") (pintype "passive"))
    )
    (net (code "30") (name "Net-(U1-XCLR)") (class "Default")
      (node (ref "C30") (pin "2") (pinfunction "2_2") (pintype "passive"))
      (node (ref "R7") (pin "2") (pinfunction "2_2") (pintype "passive"))
      (node (ref "U1") (pin "H11") (pinfunction "XCLR_H11") (pintype "passive"))
    )
    (net (code "31") (name "Net-(U2-EN)") (class "Default")
      (node (ref "C25") (pin "2") (pinfunction "2_2") (pintype "passive"))
      (node (ref "R4") (pin "1") (pinfunction "1_1") (pintype "passive"))
      (node (ref "U2") (pin "1") (pinfunction "EN_1") (pintype "passive"))
    )
    (net (code "32") (name "Net-(U2-FB)") (class "Default")
      (node (ref "C26") (pin "2") (pinfunction "2_2") (pintype "passive"))
      (node (ref "R5") (pin "1") (pinfunction "1_1") (pintype "passive"))
      (node (ref "R6") (pin "2") (pinfunction "2_2") (pintype "passive"))
      (node (ref "U2") (pin "5") (pinfunction "FB_5") (pintype "passive"))
    )
    (net (code "33") (name "Net-(U2-SW)") (class "Default")
      (node (ref "L1") (pin "1") (pinfunction "1_1") (pintype "passive"))
      (node (ref "U2") (pin "3") (pinfunction "SW_3") (pintype "passive"))
    )
    (net (code "34") (name "Net-(U3-CE)") (class "Default")
      (node (ref "C37") (pin "2") (pinfunction "2_2") (pintype "passive"))
      (node (ref "R8") (pin "2") (pinfunction "2_2") (pintype "passive"))
      (node (ref "U3") (pin "3") (pinfunction "CE_3") (pintype "passive"))
    )
    (net (code "35") (name "Net-(U3-NC)") (class "Default")
      (node (ref "C38") (pin "2") (pinfunction "2_2") (pintype "passive"))
      (node (ref "U3") (pin "4") (pinfunction "NC_4") (pintype "passive"))
    )
    (net (code "36") (name "Net-(U4-CE)") (class "Default")
      (node (ref "C43") (pin "2") (pinfunction "2_2") (pintype "passive"))
      (node (ref "R14") (pin "2") (pinfunction "2_2") (pintype "passive"))
      (node (ref "R9") (pin "2") (pinfunction "2_2") (pintype "passive"))
      (node (ref "U4") (pin "3") (pinfunction "CE_3") (pintype "passive"))
    )
    (net (code "37") (name "Net-(U4-NC)") (class "Default")
      (node (ref "C44") (pin "2") (pinfunction "2_2") (pintype "passive"))
      (node (ref "U4") (pin "4") (pinfunction "NC_4") (pintype "passive"))
    )
    (net (code "38") (name "Net-(U5-CE)") (class "Default")
      (node (ref "C49") (pin "2") (pinfunction "2_2") (pintype "passive"))
      (node (ref "R15") (pin "2") (pinfunction "2_2") (pintype "passive"))
      (node (ref "R16") (pin "2") (pinfunction "2_2") (pintype "passive"))
      (node (ref "U5") (pin "3") (pinfunction "CE_3") (pintype "passive"))
    )
    (net (code "39") (name "Net-(U5-NC)") (class "Default")
      (node (ref "C50") (pin "2") (pinfunction "2_2") (pintype "passive"))
      (node (ref "U5") (pin "4") (pinfunction "NC_4") (pintype "passive"))
    )
    (net (code "40") (name "Net-(X1-OUT)") (class "Default")
      (node (ref "R1") (pin "1") (pinfunction "1_1") (pintype "passive"))
      (node (ref "X1") (pin "3") (pinfunction "OUT_3") (pintype "passive"))
    )
    (net (code "41") (name "VDD_3V3") (class "Default")
      (node (ref "C22") (pin "2") (pinfunction "2_2") (pintype "passive"))
      (node (ref "C23") (pin "2") (pinfunction "2_2") (pintype "passive"))
      (node (ref "C24") (pin "2") (pinfunction "2_2") (pintype "passive"))
      (node (ref "C31") (pin "2") (pinfunction "2_2") (pintype "passive"))
      (node (ref "C32") (pin "2") (pinfunction "2_2") (pintype "passive"))
      (node (ref "C39") (pin "2") (pinfunction "2_2") (pintype "passive"))
      (node (ref "C40") (pin "2") (pinfunction "2_2") (pintype "passive"))
      (node (ref "C45") (pin "2") (pinfunction "2_2") (pintype "passive"))
      (node (ref "C46") (pin "2") (pinfunction "2_2") (pintype "passive"))
      (node (ref "FB1") (pin "2") (pinfunction "2_2") (pintype "passive"))
      (node (ref "R10") (pin "2") (pinfunction "2_2") (pintype "passive"))
      (node (ref "R11") (pin "2") (pinfunction "2_2") (pintype "passive"))
      (node (ref "R15") (pin "1") (pinfunction "1_1") (pintype "passive"))
      (node (ref "R17") (pin "2") (pinfunction "2_2") (pintype "passive"))
      (node (ref "R9") (pin "1") (pinfunction "1_1") (pintype "passive"))
      (node (ref "U3") (pin "1") (pinfunction "VIN_1") (pintype "passive"))
      (node (ref "U4") (pin "1") (pinfunction "VIN_1") (pintype "passive"))
      (node (ref "U5") (pin "1") (pinfunction "VIN_1") (pintype "passive"))
    )
    (net (code "42") (name "VDD_5V") (class "Default")
      (node (ref "C17") (pin "2") (pinfunction "2_2") (pintype "passive"))
      (node (ref "C18") (pin "2") (pinfunction "2_2") (pintype "passive"))
      (node (ref "FPC1") (pin "1") (pinfunction "1_1") (pintype "passive"))
      (node (ref "FPC1") (pin "2") (pinfunction "2_2") (pintype "passive"))
      (node (ref "FPC1") (pin "3") (pinfunction "3_3") (pintype "passive"))
      (node (ref "R4") (pin "2") (pinfunction "2_2") (pintype "passive"))
      (node (ref "U2") (pin "4") (pinfunction "VIN_4") (pintype "passive"))
    )
    (net (code "43") (name "unconnected-(FPC1-Pad13)") (class "Default")
      (node (ref "FPC1") (pin "13") (pinfunction "13_13") (pintype "passive+no_connect"))
    )
    (net (code "44") (name "unconnected-(FPC1-Pad14)") (class "Default")
      (node (ref "FPC1") (pin "14") (pinfunction "14_14") (pintype "passive+no_connect"))
    )
    (net (code "45") (name "unconnected-(U1-N.C.-PadA8)") (class "Default")
      (node (ref "U1") (pin "A8") (pinfunction "N.C._A8") (pintype "passive+no_connect"))
    )
    (net (code "46") (name "unconnected-(U1-N.C.-PadB8)") (class "Default")
      (node (ref "U1") (pin "B8") (pinfunction "N.C._B8") (pintype "passive+no_connect"))
    )
    (net (code "47") (name "unconnected-(U1-N.C.-PadC3)") (class "Default")
      (node (ref "U1") (pin "C3") (pinfunction "N.C._C3") (pintype "passive+no_connect"))
    )
    (net (code "48") (name "unconnected-(U1-N.C.-PadC5)") (class "Default")
      (node (ref "U1") (pin "C5") (pinfunction "N.C._C5") (pintype "passive+no_connect"))
    )
    (net (code "49") (name "unconnected-(U1-N.C.-PadC6)") (class "Default")
      (node (ref "U1") (pin "C6") (pinfunction "N.C._C6") (pintype "passive+no_connect"))
    )
    (net (code "50") (name "unconnected-(U1-N.C.-PadC7)") (class "Default")
      (node (ref "U1") (pin "C7") (pinfunction "N.C._C7") (pintype "passive+no_connect"))
    )
    (net (code "51") (name "unconnected-(U1-N.C.-PadC8)") (class "Default")
      (node (ref "U1") (pin "C8") (pinfunction "N.C._C8") (pintype "passive+no_connect"))
    )
    (net (code "52") (name "unconnected-(U1-N.C.-PadC9)") (class "Default")
      (node (ref "U1") (pin "C9") (pinfunction "N.C._C9") (pintype "passive+no_connect"))
    )
    (net (code "53") (name "unconnected-(U1-N.C.-PadD3)") (class "Default")
      (node (ref "U1") (pin "D3") (pinfunction "N.C._D3") (pintype "passive+no_connect"))
    )
    (net (code "54") (name "unconnected-(U1-N.C.-PadD9)") (class "Default")
      (node (ref "U1") (pin "D9") (pinfunction "N.C._D9") (pintype "passive+no_connect"))
    )
    (net (code "55") (name "unconnected-(U1-N.C.-PadE3)") (class "Default")
      (node (ref "U1") (pin "E3") (pinfunction "N.C._E3") (pintype "passive+no_connect"))
    )
    (net (code "56") (name "unconnected-(U1-N.C.-PadE9)") (class "Default")
      (node (ref "U1") (pin "E9") (pinfunction "N.C._E9") (pintype "passive+no_connect"))
    )
    (net (code "57") (name "unconnected-(U1-N.C.-PadE10)") (class "Default")
      (node (ref "U1") (pin "E10") (pinfunction "N.C._E10") (pintype "passive+no_connect"))
    )
    (net (code "58") (name "unconnected-(U1-N.C.-PadE11)") (class "Default")
      (node (ref "U1") (pin "E11") (pinfunction "N.C._E11") (pintype "passive+no_connect"))
    )
    (net (code "59") (name "unconnected-(U1-N.C.-PadK3)") (class "Default")
      (node (ref "U1") (pin "K3") (pinfunction "N.C._K3") (pintype "passive+no_connect"))
    )
    (net (code "60") (name "unconnected-(U1-N.C.-PadK4)") (class "Default")
      (node (ref "U1") (pin "K4") (pinfunction "N.C._K4") (pintype "passive+no_connect"))
    )
    (net (code "61") (name "unconnected-(U1-N.C.-PadK6)") (class "Default")
      (node (ref "U1") (pin "K6") (pinfunction "N.C._K6") (pintype "passive+no_connect"))
    )
    (net (code "62") (name "unconnected-(U1-N.C.-PadK9)") (class "Default")
      (node (ref "U1") (pin "K9") (pinfunction "N.C._K9") (pintype "passive+no_connect"))
    )
    (net (code "63") (name "unconnected-(U1-N.C.-PadL3)") (class "Default")
      (node (ref "U1") (pin "L3") (pinfunction "N.C._L3") (pintype "passive+no_connect"))
    )
    (net (code "64") (name "unconnected-(U1-N.C.-PadL4)") (class "Default")
      (node (ref "U1") (pin "L4") (pinfunction "N.C._L4") (pintype "passive+no_connect"))
    )
    (net (code "65") (name "unconnected-(U1-N.C.-PadL6)") (class "Default")
      (node (ref "U1") (pin "L6") (pinfunction "N.C._L6") (pintype "passive+no_connect"))
    )
    (net (code "66") (name "unconnected-(U1-N.C.-PadL9)") (class "Default")
      (node (ref "U1") (pin "L9") (pinfunction "N.C._L9") (pintype "passive+no_connect"))
    )
    (net (code "67") (name "unconnected-(U1-N.C.-PadM3)") (class "Default")
      (node (ref "U1") (pin "M3") (pinfunction "N.C._M3") (pintype "passive+no_connect"))
    )
    (net (code "68") (name "unconnected-(U1-N.C.-PadM4)") (class "Default")
      (node (ref "U1") (pin "M4") (pinfunction "N.C._M4") (pintype "passive+no_connect"))
    )
    (net (code "69") (name "unconnected-(U1-N.C.-PadM5)") (class "Default")
      (node (ref "U1") (pin "M5") (pinfunction "N.C._M5") (pintype "passive+no_connect"))
    )
    (net (code "70") (name "unconnected-(U1-N.C.-PadM6)") (class "Default")
      (node (ref "U1") (pin "M6") (pinfunction "N.C._M6") (pintype "passive+no_connect"))
    )
    (net (code "71") (name "unconnected-(U1-N.C.-PadM7)") (class "Default")
      (node (ref "U1") (pin "M7") (pinfunction "N.C._M7") (pintype "passive+no_connect"))
    )
    (net (code "72") (name "unconnected-(U1-N.C.-PadM8)") (class "Default")
      (node (ref "U1") (pin "M8") (pinfunction "N.C._M8") (pintype "passive+no_connect"))
    )
    (net (code "73") (name "unconnected-(U1-N.C.-PadM9)") (class "Default")
      (node (ref "U1") (pin "M9") (pinfunction "N.C._M9") (pintype "passive+no_connect"))
    )
    (net (code "74") (name "unconnected-(U1-TENABLE-PadG10)") (class "Default")
      (node (ref "U1") (pin "G10") (pinfunction "TENABLE_G10") (pintype "passive+no_connect"))
    )
    (net (code "75") (name "unconnected-(U1-TOUT-PadL10)") (class "Default")
      (node (ref "U1") (pin "L10") (pinfunction "TOUT_L10") (pintype "passive+no_connect"))
    )
    (net (code "76") (name "unconnected-(U1-TVMON-PadC4)") (class "Default")
      (node (ref "U1") (pin "C4") (pinfunction "TVMON_C4") (pintype "passive+no_connect"))
    )
    (net (code "77") (name "unconnected-(U1-XHS-PadL11)") (class "Default")
      (node (ref "U1") (pin "L11") (pinfunction "XHS_L11") (pintype "passive+no_connect"))
    )
    (net (code "78") (name "unconnected-(U1-XVS-PadK11)") (class "Default")
      (node (ref "U1") (pin "K11") (pinfunction "XVS_K11") (pintype "passive+no_connect"))
    )
    (net (code "79") (name "unconnected-(X1-EN{slash}NC-Pad1)") (class "Default")
      (node (ref "X1") (pin "1") (pinfunction "EN/NC_1") (pintype "passive+no_connect"))
    )
  )
)
